# 13thISE_ver5.net
KiCad netlist of a schematic drawn in EAGLE
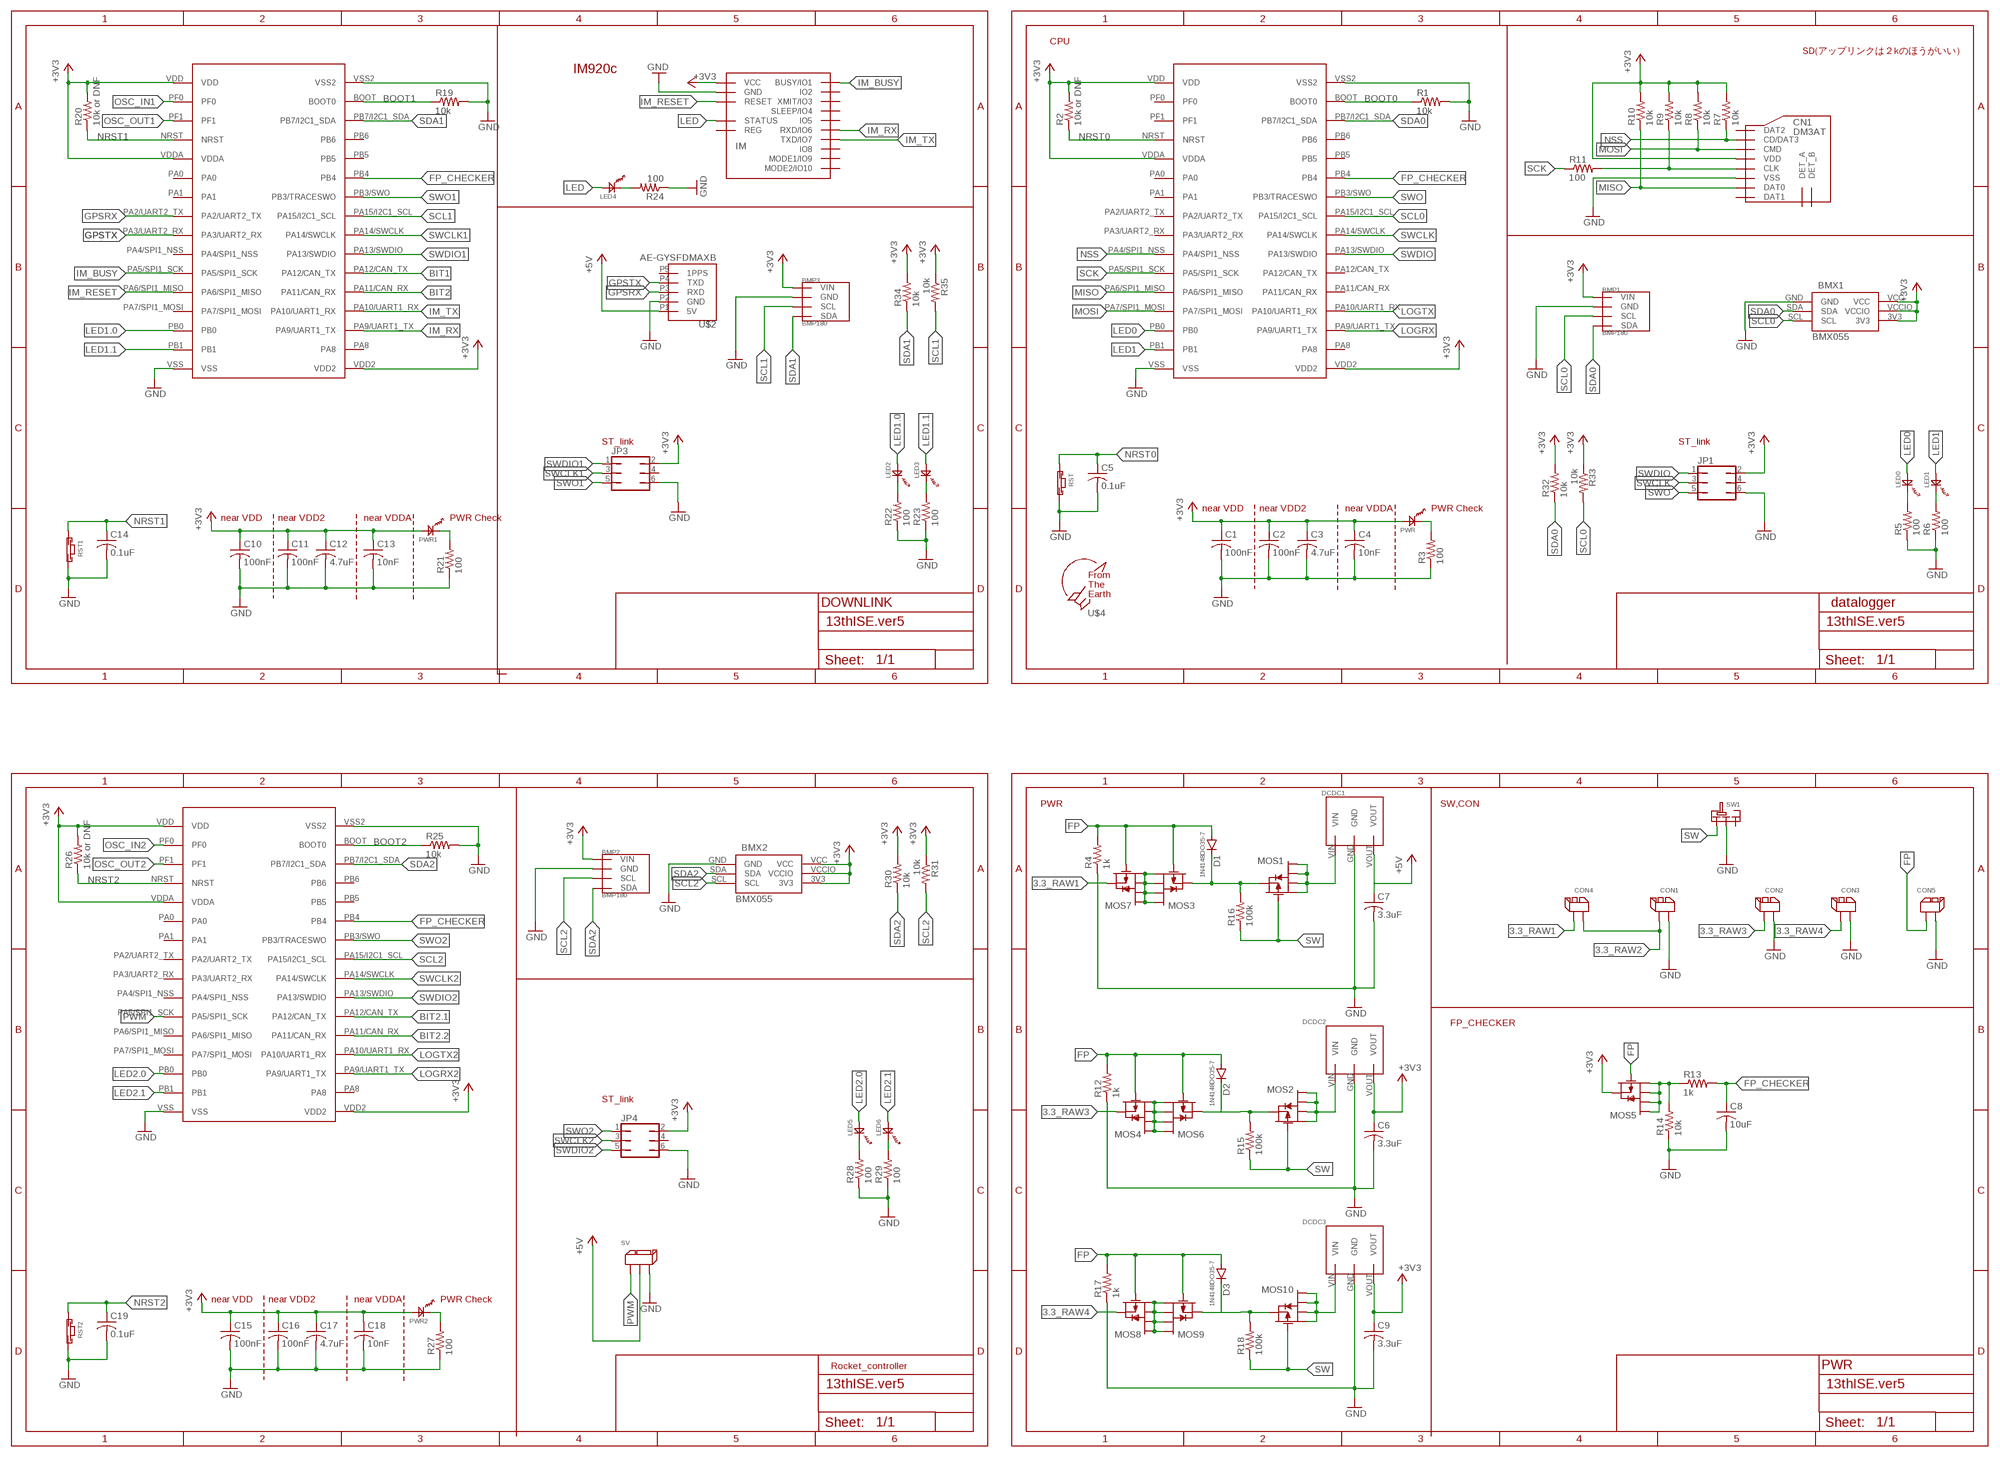
[diagram p0: schematic, sheet 1]

(export (version "E")
  (design (tool "Eeschema 10.0.6"))
  (components
    (comp (ref "BMP1")
      (value "BMP180")
      (footprint "eagle-import:GY-68")
      (libsource (lib "eagle-import") (part "BMP180"))
    )
    (comp (ref "BMP2")
      (value "BMP180")
      (footprint "eagle-import:GY-68")
      (libsource (lib "eagle-import") (part "BMP180"))
    )
    (comp (ref "BMP3")
      (value "BMP180")
      (footprint "eagle-import:GY-68")
      (libsource (lib "eagle-import") (part "BMP180"))
    )
    (comp (ref "BMX1")
      (value "BMX055")
      (footprint "eagle-import:BMX055")
      (libsource (lib "eagle-import") (part "BMX055"))
    )
    (comp (ref "BMX2")
      (value "BMX055")
      (footprint "eagle-import:BMX055")
      (libsource (lib "eagle-import") (part "BMX055"))
    )
    (comp (ref "C1")
      (value "100nF")
      (footprint "eagle-import:C1608")
      (libsource (lib "eagle-import") (part "C-USC1608"))
    )
    (comp (ref "C2")
      (value "100nF")
      (footprint "eagle-import:C1608")
      (libsource (lib "eagle-import") (part "C-USC1608"))
    )
    (comp (ref "C3")
      (value "4.7uF")
      (footprint "eagle-import:C1608")
      (libsource (lib "eagle-import") (part "C-USC1608"))
    )
    (comp (ref "C4")
      (value "10nF")
      (footprint "eagle-import:C1608")
      (libsource (lib "eagle-import") (part "C-USC1608"))
    )
    (comp (ref "C5")
      (value "0.1uF")
      (footprint "eagle-import:C1608")
      (libsource (lib "eagle-import") (part "C-USC1608"))
    )
    (comp (ref "C6")
      (value "3.3uF")
      (footprint "eagle-import:C0603")
      (libsource (lib "eagle-import") (part "C-USC0603"))
    )
    (comp (ref "C7")
      (value "3.3uF")
      (footprint "eagle-import:C0603")
      (libsource (lib "eagle-import") (part "C-USC0603"))
    )
    (comp (ref "C8")
      (value "10uF")
      (footprint "eagle-import:C0603")
      (libsource (lib "eagle-import") (part "C-USC0603"))
    )
    (comp (ref "C9")
      (value "3.3uF")
      (footprint "eagle-import:C0603")
      (libsource (lib "eagle-import") (part "C-USC0603"))
    )
    (comp (ref "C10")
      (value "100nF")
      (footprint "eagle-import:C1608")
      (libsource (lib "eagle-import") (part "C-USC1608"))
    )
    (comp (ref "C11")
      (value "100nF")
      (footprint "eagle-import:C1608")
      (libsource (lib "eagle-import") (part "C-USC1608"))
    )
    (comp (ref "C12")
      (value "4.7uF")
      (footprint "eagle-import:C1608")
      (libsource (lib "eagle-import") (part "C-USC1608"))
    )
    (comp (ref "C13")
      (value "10nF")
      (footprint "eagle-import:C1608")
      (libsource (lib "eagle-import") (part "C-USC1608"))
    )
    (comp (ref "C14")
      (value "0.1uF")
      (footprint "eagle-import:C1608")
      (libsource (lib "eagle-import") (part "C-USC1608"))
    )
    (comp (ref "C15")
      (value "100nF")
      (footprint "eagle-import:C1608")
      (libsource (lib "eagle-import") (part "C-USC1608"))
    )
    (comp (ref "C16")
      (value "100nF")
      (footprint "eagle-import:C1608")
      (libsource (lib "eagle-import") (part "C-USC1608"))
    )
    (comp (ref "C17")
      (value "4.7uF")
      (footprint "eagle-import:C1608")
      (libsource (lib "eagle-import") (part "C-USC1608"))
    )
    (comp (ref "C18")
      (value "10nF")
      (footprint "eagle-import:C1608")
      (libsource (lib "eagle-import") (part "C-USC1608"))
    )
    (comp (ref "C19")
      (value "0.1uF")
      (footprint "eagle-import:C1608")
      (libsource (lib "eagle-import") (part "C-USC1608"))
    )
    (comp (ref "CN1")
      (value "DM3AT")
      (footprint "eagle-import:DM3AT")
      (libsource (lib "eagle-import") (part "DM3AT"))
    )
    (comp (ref "CON1")
      (value "2PIN")
      (footprint "eagle-import:2PIN")
      (libsource (lib "eagle-import") (part "2PIN"))
    )
    (comp (ref "CON2")
      (value "2PIN")
      (footprint "eagle-import:2PIN")
      (libsource (lib "eagle-import") (part "2PIN"))
    )
    (comp (ref "CON3")
      (value "2PIN")
      (footprint "eagle-import:2PIN")
      (libsource (lib "eagle-import") (part "2PIN"))
    )
    (comp (ref "CON4")
      (value "2PIN")
      (footprint "eagle-import:2PIN")
      (libsource (lib "eagle-import") (part "2PIN"))
    )
    (comp (ref "CON5")
      (value "2PIN")
      (footprint "eagle-import:2PIN")
      (libsource (lib "eagle-import") (part "2PIN"))
    )
    (comp (ref "D1")
      (value "1N4148DO35-7")
      (footprint "eagle-import:DO35-7")
      (libsource (lib "eagle-import") (part "1N4148DO35-7"))
    )
    (comp (ref "D2")
      (value "1N4148DO35-7")
      (footprint "eagle-import:DO35-7")
      (libsource (lib "eagle-import") (part "1N4148DO35-7"))
    )
    (comp (ref "D3")
      (value "1N4148DO35-7")
      (footprint "eagle-import:DO35-7")
      (libsource (lib "eagle-import") (part "1N4148DO35-7"))
    )
    (comp (ref "DCDC1")
      (value "5V1A_M78AR05-1")
      (footprint "eagle-import:5V1A_M78AR05-1")
      (libsource (lib "eagle-import") (part "5V1A_M78AR05-1"))
    )
    (comp (ref "DCDC2")
      (value "3.3V1A_M78AR033-1")
      (footprint "eagle-import:3.3V1A_M78AR033-1")
      (libsource (lib "eagle-import") (part "3.3V1A_M78AR033-1"))
    )
    (comp (ref "DCDC3")
      (value "3.3V1A_M78AR033-1")
      (footprint "eagle-import:3.3V1A_M78AR033-1")
      (libsource (lib "eagle-import") (part "3.3V1A_M78AR033-1"))
    )
    (comp (ref "IM")
      (value "IM920C")
      (footprint "eagle-import:IM920C")
      (libsource (lib "eagle-import") (part "IM920C"))
    )
    (comp (ref "JP1")
      (value "JP3Q")
      (footprint "eagle-import:JP3Q")
      (libsource (lib "eagle-import") (part "JP3Q"))
    )
    (comp (ref "JP3")
      (value "JP3Q")
      (footprint "eagle-import:JP3Q")
      (libsource (lib "eagle-import") (part "JP3Q"))
    )
    (comp (ref "JP4")
      (value "JP3Q")
      (footprint "eagle-import:JP3Q")
      (libsource (lib "eagle-import") (part "JP3Q"))
    )
    (comp (ref "LED0")
      (value "OSXX1608C1A")
      (footprint "eagle-import:OSXX1608C1A")
      (libsource (lib "eagle-import") (part "OSXX1608C1A"))
    )
    (comp (ref "LED1")
      (value "OSXX1608C1A")
      (footprint "eagle-import:OSXX1608C1A")
      (libsource (lib "eagle-import") (part "OSXX1608C1A"))
    )
    (comp (ref "LED2")
      (value "OSXX1608C1A")
      (footprint "eagle-import:OSXX1608C1A")
      (libsource (lib "eagle-import") (part "OSXX1608C1A"))
    )
    (comp (ref "LED3")
      (value "OSXX1608C1A")
      (footprint "eagle-import:OSXX1608C1A")
      (libsource (lib "eagle-import") (part "OSXX1608C1A"))
    )
    (comp (ref "LED4")
      (value "OSXX1608C1A")
      (footprint "eagle-import:OSXX1608C1A")
      (libsource (lib "eagle-import") (part "OSXX1608C1A"))
    )
    (comp (ref "LED5")
      (value "OSXX1608C1A")
      (footprint "eagle-import:OSXX1608C1A")
      (libsource (lib "eagle-import") (part "OSXX1608C1A"))
    )
    (comp (ref "LED6")
      (value "OSXX1608C1A")
      (footprint "eagle-import:OSXX1608C1A")
      (libsource (lib "eagle-import") (part "OSXX1608C1A"))
    )
    (comp (ref "MOS1")
      (value "PCH_SSM6J808R")
      (footprint "eagle-import:SSM6J808R")
      (libsource (lib "eagle-import") (part "PCH_SSM6J808R"))
    )
    (comp (ref "MOS2")
      (value "PCH_SSM6J808R")
      (footprint "eagle-import:SSM6J808R")
      (libsource (lib "eagle-import") (part "PCH_SSM6J808R"))
    )
    (comp (ref "MOS3")
      (value "PCH_SSM6J808R")
      (footprint "eagle-import:SSM6J808R")
      (libsource (lib "eagle-import") (part "PCH_SSM6J808R"))
    )
    (comp (ref "MOS4")
      (value "PCH_SSM6J808R")
      (footprint "eagle-import:SSM6J808R")
      (libsource (lib "eagle-import") (part "PCH_SSM6J808R"))
    )
    (comp (ref "MOS5")
      (value "PCH_SSM6J808R")
      (footprint "eagle-import:SSM6J808R")
      (libsource (lib "eagle-import") (part "PCH_SSM6J808R"))
    )
    (comp (ref "MOS6")
      (value "PCH_SSM6J808R")
      (footprint "eagle-import:SSM6J808R")
      (libsource (lib "eagle-import") (part "PCH_SSM6J808R"))
    )
    (comp (ref "MOS7")
      (value "PCH_SSM6J808R")
      (footprint "eagle-import:SSM6J808R")
      (libsource (lib "eagle-import") (part "PCH_SSM6J808R"))
    )
    (comp (ref "MOS8")
      (value "PCH_SSM6J808R")
      (footprint "eagle-import:SSM6J808R")
      (libsource (lib "eagle-import") (part "PCH_SSM6J808R"))
    )
    (comp (ref "MOS9")
      (value "PCH_SSM6J808R")
      (footprint "eagle-import:SSM6J808R")
      (libsource (lib "eagle-import") (part "PCH_SSM6J808R"))
    )
    (comp (ref "MOS10")
      (value "PCH_SSM6J808R")
      (footprint "eagle-import:SSM6J808R")
      (libsource (lib "eagle-import") (part "PCH_SSM6J808R"))
    )
    (comp (ref "PWR")
      (value "OSXX1608C1A")
      (footprint "eagle-import:OSXX1608C1A")
      (libsource (lib "eagle-import") (part "OSXX1608C1A"))
    )
    (comp (ref "PWR1")
      (value "OSXX1608C1A")
      (footprint "eagle-import:OSXX1608C1A")
      (libsource (lib "eagle-import") (part "OSXX1608C1A"))
    )
    (comp (ref "PWR2")
      (value "OSXX1608C1A")
      (footprint "eagle-import:OSXX1608C1A")
      (libsource (lib "eagle-import") (part "OSXX1608C1A"))
    )
    (comp (ref "R1")
      (value "10k")
      (footprint "eagle-import:R0603")
      (libsource (lib "eagle-import") (part "R-US_R0603"))
    )
    (comp (ref "R2")
      (value "10k or DNF")
      (footprint "eagle-import:R0603")
      (libsource (lib "eagle-import") (part "R-US_R0603"))
    )
    (comp (ref "R3")
      (value "100")
      (footprint "eagle-import:R0603")
      (libsource (lib "eagle-import") (part "R-US_R0603"))
    )
    (comp (ref "R4")
      (value "1k")
      (footprint "eagle-import:R0603")
      (libsource (lib "eagle-import") (part "R-US_R0603"))
    )
    (comp (ref "R5")
      (value "100")
      (footprint "eagle-import:R0603")
      (libsource (lib "eagle-import") (part "R-US_R0603"))
    )
    (comp (ref "R6")
      (value "100")
      (footprint "eagle-import:R0603")
      (libsource (lib "eagle-import") (part "R-US_R0603"))
    )
    (comp (ref "R7")
      (value "10k")
      (footprint "eagle-import:R0603")
      (libsource (lib "eagle-import") (part "R-US_R0603"))
    )
    (comp (ref "R8")
      (value "10k")
      (footprint "eagle-import:R0603")
      (libsource (lib "eagle-import") (part "R-US_R0603"))
    )
    (comp (ref "R9")
      (value "10k")
      (footprint "eagle-import:R0603")
      (libsource (lib "eagle-import") (part "R-US_R0603"))
    )
    (comp (ref "R10")
      (value "10k")
      (footprint "eagle-import:R0603")
      (libsource (lib "eagle-import") (part "R-US_R0603"))
    )
    (comp (ref "R11")
      (value "100")
      (footprint "eagle-import:R0603")
      (libsource (lib "eagle-import") (part "R-US_R0603"))
    )
    (comp (ref "R12")
      (value "1k")
      (footprint "eagle-import:R0603")
      (libsource (lib "eagle-import") (part "R-US_R0603"))
    )
    (comp (ref "R13")
      (value "1k")
      (footprint "eagle-import:R0603")
      (libsource (lib "eagle-import") (part "R-US_R0603"))
    )
    (comp (ref "R14")
      (value "10k")
      (footprint "eagle-import:R0603")
      (libsource (lib "eagle-import") (part "R-US_R0603"))
    )
    (comp (ref "R15")
      (value "100k")
      (footprint "eagle-import:R0603")
      (libsource (lib "eagle-import") (part "R-US_R0603"))
    )
    (comp (ref "R16")
      (value "100k")
      (footprint "eagle-import:R0603")
      (libsource (lib "eagle-import") (part "R-US_R0603"))
    )
    (comp (ref "R17")
      (value "1k")
      (footprint "eagle-import:R0603")
      (libsource (lib "eagle-import") (part "R-US_R0603"))
    )
    (comp (ref "R18")
      (value "100k")
      (footprint "eagle-import:R0603")
      (libsource (lib "eagle-import") (part "R-US_R0603"))
    )
    (comp (ref "R19")
      (value "10k")
      (footprint "eagle-import:R0603")
      (libsource (lib "eagle-import") (part "R-US_R0603"))
    )
    (comp (ref "R20")
      (value "10k or DNF")
      (footprint "eagle-import:R0603")
      (libsource (lib "eagle-import") (part "R-US_R0603"))
    )
    (comp (ref "R21")
      (value "100")
      (footprint "eagle-import:R0603")
      (libsource (lib "eagle-import") (part "R-US_R0603"))
    )
    (comp (ref "R22")
      (value "100")
      (footprint "eagle-import:R0603")
      (libsource (lib "eagle-import") (part "R-US_R0603"))
    )
    (comp (ref "R23")
      (value "100")
      (footprint "eagle-import:R0603")
      (libsource (lib "eagle-import") (part "R-US_R0603"))
    )
    (comp (ref "R24")
      (value "100")
      (footprint "eagle-import:R0603")
      (libsource (lib "eagle-import") (part "R-US_R0603"))
    )
    (comp (ref "R25")
      (value "10k")
      (footprint "eagle-import:R0603")
      (libsource (lib "eagle-import") (part "R-US_R0603"))
    )
    (comp (ref "R26")
      (value "10k or DNF")
      (footprint "eagle-import:R0603")
      (libsource (lib "eagle-import") (part "R-US_R0603"))
    )
    (comp (ref "R27")
      (value "100")
      (footprint "eagle-import:R0603")
      (libsource (lib "eagle-import") (part "R-US_R0603"))
    )
    (comp (ref "R28")
      (value "100")
      (footprint "eagle-import:R0603")
      (libsource (lib "eagle-import") (part "R-US_R0603"))
    )
    (comp (ref "R29")
      (value "100")
      (footprint "eagle-import:R0603")
      (libsource (lib "eagle-import") (part "R-US_R0603"))
    )
    (comp (ref "R30")
      (value "10k")
      (footprint "eagle-import:R0603")
      (libsource (lib "eagle-import") (part "R-US_R0603"))
    )
    (comp (ref "R31")
      (value "10k")
      (footprint "eagle-import:R0603")
      (libsource (lib "eagle-import") (part "R-US_R0603"))
    )
    (comp (ref "R32")
      (value "10k")
      (footprint "eagle-import:R0603")
      (libsource (lib "eagle-import") (part "R-US_R0603"))
    )
    (comp (ref "R33")
      (value "10k")
      (footprint "eagle-import:R0603")
      (libsource (lib "eagle-import") (part "R-US_R0603"))
    )
    (comp (ref "R34")
      (value "10k")
      (footprint "eagle-import:R0603")
      (libsource (lib "eagle-import") (part "R-US_R0603"))
    )
    (comp (ref "R35")
      (value "10k")
      (footprint "eagle-import:R0603")
      (libsource (lib "eagle-import") (part "R-US_R0603"))
    )
    (comp (ref "RST")
      (value "TVAF06-A020B-R")
      (footprint "eagle-import:TVAF06-A020B-R")
      (libsource (lib "eagle-import") (part "TVAF06-A020B-R"))
    )
    (comp (ref "RST1")
      (value "TVAF06-A020B-R")
      (footprint "eagle-import:TVAF06-A020B-R")
      (libsource (lib "eagle-import") (part "TVAF06-A020B-R"))
    )
    (comp (ref "RST2")
      (value "TVAF06-A020B-R")
      (footprint "eagle-import:TVAF06-A020B-R")
      (libsource (lib "eagle-import") (part "TVAF06-A020B-R"))
    )
    (comp (ref "STM0")
      (value "STM32F303K8")
      (footprint "eagle-import:STM32F303K8")
      (libsource (lib "eagle-import") (part "STM32F303K8"))
    )
    (comp (ref "STM1")
      (value "STM32F303K8")
      (footprint "eagle-import:STM32F303K8")
      (libsource (lib "eagle-import") (part "STM32F303K8"))
    )
    (comp (ref "SV")
      (value "3PIN")
      (footprint "eagle-import:3PIN")
      (libsource (lib "eagle-import") (part "3PIN"))
    )
    (comp (ref "SW1")
      (value "SRIDE_SWITCH")
      (footprint "eagle-import:SRIDE_SWITCH")
      (libsource (lib "eagle-import") (part "SRIDE_SWITCH"))
    )
    (comp (ref "U$1")
      (value "STM32F303K8")
      (footprint "eagle-import:STM32F303K8")
      (libsource (lib "eagle-import") (part "STM32F303K8"))
    )
    (comp (ref "U$2")
      (value "AE-GYSFDMAXB")
      (footprint "eagle-import:AE-GYSFDMAXB")
      (libsource (lib "eagle-import") (part "AE-GYSFDMAXB"))
    )
    (comp (ref "U$4")
      (value "F.T.E.LOGO")
      (footprint "eagle-import:LOGO")
      (libsource (lib "eagle-import") (part "F.T.E.LOGO"))
    )
  )
  (nets
    (net (code "1") (name "+3V3") (class "Default")
      (node (ref "BMP1") (pin "P1") (pinfunction "VIN_P1") (pintype "bidirectional"))
      (node (ref "BMP2") (pin "P1") (pinfunction "VIN_P1") (pintype "bidirectional"))
      (node (ref "BMP3") (pin "P1") (pinfunction "VIN_P1") (pintype "bidirectional"))
      (node (ref "BMX1") (pin "3V3") (pinfunction "3V3_3V3") (pintype "power_in"))
      (node (ref "BMX1") (pin "VCC") (pinfunction "VCC_VCC") (pintype "power_in"))
      (node (ref "BMX1") (pin "VCCIO") (pinfunction "VCCIO_VCCIO") (pintype "power_in"))
      (node (ref "BMX2") (pin "3V3") (pinfunction "3V3_3V3") (pintype "power_in"))
      (node (ref "BMX2") (pin "VCC") (pinfunction "VCC_VCC") (pintype "power_in"))
      (node (ref "BMX2") (pin "VCCIO") (pinfunction "VCCIO_VCCIO") (pintype "power_in"))
      (node (ref "C1") (pin "1") (pinfunction "1_1") (pintype "passive"))
      (node (ref "C10") (pin "1") (pinfunction "1_1") (pintype "passive"))
      (node (ref "C11") (pin "1") (pinfunction "1_1") (pintype "passive"))
      (node (ref "C12") (pin "1") (pinfunction "1_1") (pintype "passive"))
      (node (ref "C13") (pin "1") (pinfunction "1_1") (pintype "passive"))
      (node (ref "C15") (pin "1") (pinfunction "1_1") (pintype "passive"))
      (node (ref "C16") (pin "1") (pinfunction "1_1") (pintype "passive"))
      (node (ref "C17") (pin "1") (pinfunction "1_1") (pintype "passive"))
      (node (ref "C18") (pin "1") (pinfunction "1_1") (pintype "passive"))
      (node (ref "C2") (pin "1") (pinfunction "1_1") (pintype "passive"))
      (node (ref "C3") (pin "1") (pinfunction "1_1") (pintype "passive"))
      (node (ref "C4") (pin "1") (pinfunction "1_1") (pintype "passive"))
      (node (ref "C6") (pin "1") (pinfunction "1_1") (pintype "passive"))
      (node (ref "C9") (pin "1") (pinfunction "1_1") (pintype "passive"))
      (node (ref "CN1") (pin "VDD") (pinfunction "VDD_VDD") (pintype "bidirectional"))
      (node (ref "DCDC2") (pin "VOUT") (pinfunction "VOUT_VOUT") (pintype "bidirectional"))
      (node (ref "DCDC3") (pin "VOUT") (pinfunction "VOUT_VOUT") (pintype "bidirectional"))
      (node (ref "IM") (pin "$P17") (pinfunction "VCC_$P17") (pintype "bidirectional"))
      (node (ref "JP1") (pin "2") (pinfunction "2_2") (pintype "passive"))
      (node (ref "JP3") (pin "2") (pinfunction "2_2") (pintype "passive"))
      (node (ref "JP4") (pin "2") (pinfunction "2_2") (pintype "passive"))
      (node (ref "MOS5") (pin "4") (pinfunction "4_4") (pintype "bidirectional"))
      (node (ref "PWR") (pin "AN") (pinfunction "AN_AN") (pintype "bidirectional"))
      (node (ref "PWR1") (pin "AN") (pinfunction "AN_AN") (pintype "bidirectional"))
      (node (ref "PWR2") (pin "AN") (pinfunction "AN_AN") (pintype "bidirectional"))
      (node (ref "R10") (pin "2") (pinfunction "2_2") (pintype "passive"))
      (node (ref "R2") (pin "2") (pinfunction "2_2") (pintype "passive"))
      (node (ref "R20") (pin "2") (pinfunction "2_2") (pintype "passive"))
      (node (ref "R26") (pin "2") (pinfunction "2_2") (pintype "passive"))
      (node (ref "R30") (pin "2") (pinfunction "2_2") (pintype "passive"))
      (node (ref "R31") (pin "1") (pinfunction "1_1") (pintype "passive"))
      (node (ref "R32") (pin "2") (pinfunction "2_2") (pintype "passive"))
      (node (ref "R33") (pin "1") (pinfunction "1_1") (pintype "passive"))
      (node (ref "R34") (pin "2") (pinfunction "2_2") (pintype "passive"))
      (node (ref "R35") (pin "1") (pinfunction "1_1") (pintype "passive"))
      (node (ref "R7") (pin "2") (pinfunction "2_2") (pintype "passive"))
      (node (ref "R8") (pin "2") (pinfunction "2_2") (pintype "passive"))
      (node (ref "R9") (pin "2") (pinfunction "2_2") (pintype "passive"))
      (node (ref "STM0") (pin "VDD") (pinfunction "VDD_VDD") (pintype "power_in"))
      (node (ref "STM0") (pin "VDD2") (pinfunction "VDD2_VDD2") (pintype "power_in"))
      (node (ref "STM0") (pin "VDDA") (pinfunction "VDDA_VDDA") (pintype "power_in"))
      (node (ref "STM1") (pin "VDD") (pinfunction "VDD_VDD") (pintype "power_in"))
      (node (ref "STM1") (pin "VDD2") (pinfunction "VDD2_VDD2") (pintype "power_in"))
      (node (ref "STM1") (pin "VDDA") (pinfunction "VDDA_VDDA") (pintype "power_in"))
      (node (ref "U$1") (pin "VDD") (pinfunction "VDD_VDD") (pintype "power_in"))
      (node (ref "U$1") (pin "VDD2") (pinfunction "VDD2_VDD2") (pintype "power_in"))
      (node (ref "U$1") (pin "VDDA") (pinfunction "VDDA_VDDA") (pintype "power_in"))
    )
    (net (code "2") (name "+5V") (class "Default")
      (node (ref "C7") (pin "1") (pinfunction "1_1") (pintype "passive"))
      (node (ref "DCDC1") (pin "VOUT") (pinfunction "VOUT_VOUT") (pintype "bidirectional"))
      (node (ref "SV") (pin "P$2") (pinfunction "P$2_P$2") (pintype "bidirectional"))
      (node (ref "U$2") (pin "P1") (pinfunction "5V_P1") (pintype "bidirectional"))
    )
    (net (code "3") (name "/BOOT0") (class "Default")
      (node (ref "R1") (pin "1") (pinfunction "1_1") (pintype "passive"))
      (node (ref "STM0") (pin "BOOT") (pinfunction "BOOT0_BOOT") (pintype "bidirectional"))
    )
    (net (code "4") (name "/BOOT1") (class "Default")
      (node (ref "R19") (pin "1") (pinfunction "1_1") (pintype "passive"))
      (node (ref "STM1") (pin "BOOT") (pinfunction "BOOT0_BOOT") (pintype "bidirectional"))
    )
    (net (code "5") (name "/BOOT2") (class "Default")
      (node (ref "R25") (pin "1") (pinfunction "1_1") (pintype "passive"))
      (node (ref "U$1") (pin "BOOT") (pinfunction "BOOT0_BOOT") (pintype "bidirectional"))
    )
    (net (code "6") (name "3.3_RAW1") (class "Default")
      (node (ref "CON4") (pin "P$2") (pinfunction "P$2_P$2") (pintype "bidirectional"))
      (node (ref "MOS7") (pin "4") (pinfunction "4_4") (pintype "bidirectional"))
    )
    (net (code "7") (name "3.3_RAW2") (class "Default")
      (node (ref "CON1") (pin "P$2") (pinfunction "P$2_P$2") (pintype "bidirectional"))
      (node (ref "CON4") (pin "P$1") (pinfunction "P$1_P$1") (pintype "bidirectional"))
    )
    (net (code "8") (name "3.3_RAW3") (class "Default")
      (node (ref "CON2") (pin "P$2") (pinfunction "P$2_P$2") (pintype "bidirectional"))
      (node (ref "MOS4") (pin "4") (pinfunction "4_4") (pintype "bidirectional"))
    )
    (net (code "9") (name "3.3_RAW4") (class "Default")
      (node (ref "CON3") (pin "P$2") (pinfunction "P$2_P$2") (pintype "bidirectional"))
      (node (ref "MOS8") (pin "4") (pinfunction "4_4") (pintype "bidirectional"))
    )
    (net (code "10") (name "BIT1") (class "Default")
      (node (ref "STM1") (pin "PA12/CAN_TX") (pinfunction "PA12/CAN_TX_PA12/CAN_TX") (pintype "bidirectional"))
    )
    (net (code "11") (name "BIT2") (class "Default")
      (node (ref "STM1") (pin "PA11/CAN_RX") (pinfunction "PA11/CAN_RX_PA11/CAN_RX") (pintype "bidirectional"))
    )
    (net (code "12") (name "BIT2.1") (class "Default")
      (node (ref "U$1") (pin "PA12/CAN_TX") (pinfunction "PA12/CAN_TX_PA12/CAN_TX") (pintype "bidirectional"))
    )
    (net (code "13") (name "BIT2.2") (class "Default")
      (node (ref "U$1") (pin "PA11/CAN_RX") (pinfunction "PA11/CAN_RX_PA11/CAN_RX") (pintype "bidirectional"))
    )
    (net (code "14") (name "FP") (class "Default")
      (node (ref "CON5") (pin "P$1") (pinfunction "P$1_P$1") (pintype "bidirectional"))
      (node (ref "D1") (pin "A") (pinfunction "A_A") (pintype "passive"))
      (node (ref "D2") (pin "A") (pinfunction "A_A") (pintype "passive"))
      (node (ref "D3") (pin "A") (pinfunction "A_A") (pintype "passive"))
      (node (ref "MOS3") (pin "3") (pinfunction "3_3") (pintype "bidirectional"))
      (node (ref "MOS4") (pin "3") (pinfunction "3_3") (pintype "bidirectional"))
      (node (ref "MOS5") (pin "3") (pinfunction "3_3") (pintype "bidirectional"))
      (node (ref "MOS6") (pin "3") (pinfunction "3_3") (pintype "bidirectional"))
      (node (ref "MOS7") (pin "3") (pinfunction "3_3") (pintype "bidirectional"))
      (node (ref "MOS8") (pin "3") (pinfunction "3_3") (pintype "bidirectional"))
      (node (ref "MOS9") (pin "3") (pinfunction "3_3") (pintype "bidirectional"))
      (node (ref "R12") (pin "2") (pinfunction "2_2") (pintype "passive"))
      (node (ref "R17") (pin "2") (pinfunction "2_2") (pintype "passive"))
      (node (ref "R4") (pin "2") (pinfunction "2_2") (pintype "passive"))
    )
    (net (code "15") (name "FP_CHECKER") (class "Default")
      (node (ref "C8") (pin "1") (pinfunction "1_1") (pintype "passive"))
      (node (ref "R13") (pin "2") (pinfunction "2_2") (pintype "passive"))
      (node (ref "STM0") (pin "PB4") (pinfunction "PB4_PB4") (pintype "bidirectional"))
      (node (ref "STM1") (pin "PB4") (pinfunction "PB4_PB4") (pintype "bidirectional"))
      (node (ref "U$1") (pin "PB4") (pinfunction "PB4_PB4") (pintype "bidirectional"))
    )
    (net (code "16") (name "GND") (class "Default")
      (node (ref "BMP1") (pin "P2") (pinfunction "GND_P2") (pintype "bidirectional"))
      (node (ref "BMP2") (pin "P2") (pinfunction "GND_P2") (pintype "bidirectional"))
      (node (ref "BMP3") (pin "P2") (pinfunction "GND_P2") (pintype "bidirectional"))
      (node (ref "BMX1") (pin "GND") (pinfunction "GND_GND") (pintype "power_in"))
      (node (ref "BMX2") (pin "GND") (pinfunction "GND_GND") (pintype "power_in"))
      (node (ref "C1") (pin "2") (pinfunction "2_2") (pintype "passive"))
      (node (ref "C10") (pin "2") (pinfunction "2_2") (pintype "passive"))
      (node (ref "C11") (pin "2") (pinfunction "2_2") (pintype "passive"))
      (node (ref "C12") (pin "2") (pinfunction "2_2") (pintype "passive"))
      (node (ref "C13") (pin "2") (pinfunction "2_2") (pintype "passive"))
      (node (ref "C14") (pin "2") (pinfunction "2_2") (pintype "passive"))
      (node (ref "C15") (pin "2") (pinfunction "2_2") (pintype "passive"))
      (node (ref "C16") (pin "2") (pinfunction "2_2") (pintype "passive"))
      (node (ref "C17") (pin "2") (pinfunction "2_2") (pintype "passive"))
      (node (ref "C18") (pin "2") (pinfunction "2_2") (pintype "passive"))
      (node (ref "C19") (pin "2") (pinfunction "2_2") (pintype "passive"))
      (node (ref "C2") (pin "2") (pinfunction "2_2") (pintype "passive"))
      (node (ref "C3") (pin "2") (pinfunction "2_2") (pintype "passive"))
      (node (ref "C4") (pin "2") (pinfunction "2_2") (pintype "passive"))
      (node (ref "C5") (pin "2") (pinfunction "2_2") (pintype "passive"))
      (node (ref "C6") (pin "2") (pinfunction "2_2") (pintype "passive"))
      (node (ref "C7") (pin "2") (pinfunction "2_2") (pintype "passive"))
      (node (ref "C8") (pin "2") (pinfunction "2_2") (pintype "passive"))
      (node (ref "C9") (pin "2") (pinfunction "2_2") (pintype "passive"))
      (node (ref "CN1") (pin "VSS") (pinfunction "VSS_VSS") (pintype "bidirectional"))
      (node (ref "CON1") (pin "P$1") (pinfunction "P$1_P$1") (pintype "bidirectional"))
      (node (ref "CON2") (pin "P$1") (pinfunction "P$1_P$1") (pintype "bidirectional"))
      (node (ref "CON3") (pin "P$1") (pinfunction "P$1_P$1") (pintype "bidirectional"))
      (node (ref "CON5") (pin "P$2") (pinfunction "P$2_P$2") (pintype "bidirectional"))
      (node (ref "DCDC1") (pin "GND") (pinfunction "GND_GND") (pintype "bidirectional"))
      (node (ref "DCDC2") (pin "GND") (pinfunction "GND_GND") (pintype "bidirectional"))
      (node (ref "DCDC3") (pin "GND") (pinfunction "GND_GND") (pintype "bidirectional"))
      (node (ref "IM") (pin "$P18") (pinfunction "GND_$P18") (pintype "bidirectional"))
      (node (ref "JP1") (pin "6") (pinfunction "6_6") (pintype "passive"))
      (node (ref "JP3") (pin "6") (pinfunction "6_6") (pintype "passive"))
      (node (ref "JP4") (pin "6") (pinfunction "6_6") (pintype "passive"))
      (node (ref "R1") (pin "2") (pinfunction "2_2") (pintype "passive"))
      (node (ref "R12") (pin "1") (pinfunction "1_1") (pintype "passive"))
      (node (ref "R14") (pin "1") (pinfunction "1_1") (pintype "passive"))
      (node (ref "R17") (pin "1") (pinfunction "1_1") (pintype "passive"))
      (node (ref "R19") (pin "2") (pinfunction "2_2") (pintype "passive"))
      (node (ref "R21") (pin "1") (pinfunction "1_1") (pintype "passive"))
      (node (ref "R22") (pin "1") (pinfunction "1_1") (pintype "passive"))
      (node (ref "R23") (pin "1") (pinfunction "1_1") (pintype "passive"))
      (node (ref "R24") (pin "1") (pinfunction "1_1") (pintype "passive"))
      (node (ref "R25") (pin "2") (pinfunction "2_2") (pintype "passive"))
      (node (ref "R27") (pin "1") (pinfunction "1_1") (pintype "passive"))
      (node (ref "R28") (pin "1") (pinfunction "1_1") (pintype "passive"))
      (node (ref "R29") (pin "1") (pinfunction "1_1") (pintype "passive"))
      (node (ref "R3") (pin "1") (pinfunction "1_1") (pintype "passive"))
      (node (ref "R4") (pin "1") (pinfunction "1_1") (pintype "passive"))
      (node (ref "R5") (pin "1") (pinfunction "1_1") (pintype "passive"))
      (node (ref "R6") (pin "1") (pinfunction "1_1") (pintype "passive"))
      (node (ref "RST") (pin "P$2") (pinfunction "P$2_P$2") (pintype "bidirectional"))
      (node (ref "RST1") (pin "P$2") (pinfunction "P$2_P$2") (pintype "bidirectional"))
      (node (ref "RST2") (pin "P$2") (pinfunction "P$2_P$2") (pintype "bidirectional"))
      (node (ref "STM0") (pin "VSS") (pinfunction "VSS_VSS") (pintype "power_in"))
      (node (ref "STM0") (pin "VSS2") (pinfunction "VSS2_VSS2") (pintype "power_in"))
      (node (ref "STM1") (pin "VSS") (pinfunction "VSS_VSS") (pintype "power_in"))
      (node (ref "STM1") (pin "VSS2") (pinfunction "VSS2_VSS2") (pintype "power_in"))
      (node (ref "SV") (pin "P$3") (pinfunction "P$3_P$3") (pintype "bidirectional"))
      (node (ref "SW1") (pin "LR") (pinfunction "LR_LR") (pintype "bidirectional"))
      (node (ref "U$1") (pin "VSS") (pinfunction "VSS_VSS") (pintype "power_in"))
      (node (ref "U$1") (pin "VSS2") (pinfunction "VSS2_VSS2") (pintype "power_in"))
      (node (ref "U$2") (pin "P2") (pinfunction "GND_P2") (pintype "bidirectional"))
    )
    (net (code "17") (name "GPSRX") (class "Default")
      (node (ref "STM1") (pin "PA2/UART2_TX") (pinfunction "PA2/UART2_TX_PA2/UART2_TX") (pintype "bidirectional"))
      (node (ref "U$2") (pin "P3") (pinfunction "RXD_P3") (pintype "bidirectional"))
    )
    (net (code "18") (name "GPSTX") (class "Default")
      (node (ref "STM1") (pin "PA3/UART2_RX") (pinfunction "PA3/UART2_RX_PA3/UART2_RX") (pintype "bidirectional"))
      (node (ref "U$2") (pin "P4") (pinfunction "TXD_P4") (pintype "bidirectional"))
    )
    (net (code "19") (name "IM_BUSY") (class "Default")
      (node (ref "IM") (pin "$P1") (pinfunction "BUSY/IO1_$P1") (pintype "bidirectional"))
      (node (ref "STM1") (pin "PA5/SPI1_SCK") (pinfunction "PA5/SPI1_SCK_PA5/SPI1_SCK") (pintype "bidirectional"))
    )
    (net (code "20") (name "IM_RESET") (class "Default")
      (node (ref "IM") (pin "$P19") (pinfunction "RESET_$P19") (pintype "bidirectional"))
      (node (ref "STM1") (pin "PA6/SPI1_MISO") (pinfunction "PA6/SPI1_MISO_PA6/SPI1_MISO") (pintype "bidirectional"))
    )
    (net (code "21") (name "IM_RX") (class "Default")
      (node (ref "IM") (pin "$P6") (pinfunction "RXD/IO6_$P6") (pintype "bidirectional"))
      (node (ref "STM1") (pin "PA9/UART1_TX") (pinfunction "PA9/UART1_TX_PA9/UART1_TX") (pintype "bidirectional"))
    )
    (net (code "22") (name "IM_TX") (class "Default")
      (node (ref "IM") (pin "$P7") (pinfunction "TXD/IO7_$P7") (pintype "bidirectional"))
      (node (ref "STM1") (pin "PA10/UART1_RX") (pinfunction "PA10/UART1_RX_PA10/UART1_RX") (pintype "bidirectional"))
    )
    (net (code "23") (name "LED") (class "Default")
      (node (ref "IM") (pin "$P15") (pinfunction "STATUS_$P15") (pintype "bidirectional"))
      (node (ref "LED4") (pin "AN") (pinfunction "AN_AN") (pintype "bidirectional"))
    )
    (net (code "24") (name "LED0") (class "Default")
      (node (ref "LED0") (pin "AN") (pinfunction "AN_AN") (pintype "bidirectional"))
      (node (ref "STM0") (pin "PB0") (pinfunction "PB0_PB0") (pintype "bidirectional"))
    )
    (net (code "25") (name "LED1") (class "Default")
      (node (ref "LED1") (pin "AN") (pinfunction "AN_AN") (pintype "bidirectional"))
      (node (ref "STM0") (pin "PB1") (pinfunction "PB1_PB1") (pintype "bidirectional"))
    )
    (net (code "26") (name "LED1.0") (class "Default")
      (node (ref "LED2") (pin "AN") (pinfunction "AN_AN") (pintype "bidirectional"))
      (node (ref "STM1") (pin "PB0") (pinfunction "PB0_PB0") (pintype "bidirectional"))
    )
    (net (code "27") (name "LED1.1") (class "Default")
      (node (ref "LED3") (pin "AN") (pinfunction "AN_AN") (pintype "bidirectional"))
      (node (ref "STM1") (pin "PB1") (pinfunction "PB1_PB1") (pintype "bidirectional"))
    )
    (net (code "28") (name "LED2.0") (class "Default")
      (node (ref "LED5") (pin "AN") (pinfunction "AN_AN") (pintype "bidirectional"))
      (node (ref "U$1") (pin "PB0") (pinfunction "PB0_PB0") (pintype "bidirectional"))
    )
    (net (code "29") (name "LED2.1") (class "Default")
      (node (ref "LED6") (pin "AN") (pinfunction "AN_AN") (pintype "bidirectional"))
      (node (ref "U$1") (pin "PB1") (pinfunction "PB1_PB1") (pintype "bidirectional"))
    )
    (net (code "30") (name "LOGRX") (class "Default")
      (node (ref "STM0") (pin "PA9/UART1_TX") (pinfunction "PA9/UART1_TX_PA9/UART1_TX") (pintype "bidirectional"))
    )
    (net (code "31") (name "LOGRX2") (class "Default")
      (node (ref "U$1") (pin "PA9/UART1_TX") (pinfunction "PA9/UART1_TX_PA9/UART1_TX") (pintype "bidirectional"))
    )
    (net (code "32") (name "LOGTX") (class "Default")
      (node (ref "STM0") (pin "PA10/UART1_RX") (pinfunction "PA10/UART1_RX_PA10/UART1_RX") (pintype "bidirectional"))
    )
    (net (code "33") (name "LOGTX2") (class "Default")
      (node (ref "U$1") (pin "PA10/UART1_RX") (pinfunction "PA10/UART1_RX_PA10/UART1_RX") (pintype "bidirectional"))
    )
    (net (code "34") (name "MISO") (class "Default")
      (node (ref "CN1") (pin "DAT0") (pinfunction "DAT0_DAT0") (pintype "bidirectional"))
      (node (ref "R10") (pin "1") (pinfunction "1_1") (pintype "passive"))
      (node (ref "STM0") (pin "PA6/SPI1_MISO") (pinfunction "PA6/SPI1_MISO_PA6/SPI1_MISO") (pintype "bidirectional"))
    )
    (net (code "35") (name "MOSI") (class "Default")
      (node (ref "CN1") (pin "CMD") (pinfunction "CMD_CMD") (pintype "bidirectional"))
      (node (ref "R8") (pin "1") (pinfunction "1_1") (pintype "passive"))
      (node (ref "STM0") (pin "PA7/SPI1_MOSI") (pinfunction "PA7/SPI1_MOSI_PA7/SPI1_MOSI") (pintype "bidirectional"))
    )
    (net (code "36") (name "NRST0") (class "Default")
      (node (ref "C5") (pin "1") (pinfunction "1_1") (pintype "passive"))
      (node (ref "R2") (pin "1") (pinfunction "1_1") (pintype "passive"))
      (node (ref "RST") (pin "P$1") (pinfunction "P$1_P$1") (pintype "bidirectional"))
      (node (ref "STM0") (pin "NRST") (pinfunction "NRST_NRST") (pintype "bidirectional"))
    )
    (net (code "37") (name "NRST1") (class "Default")
      (node (ref "C14") (pin "1") (pinfunction "1_1") (pintype "passive"))
      (node (ref "R20") (pin "1") (pinfunction "1_1") (pintype "passive"))
      (node (ref "RST1") (pin "P$1") (pinfunction "P$1_P$1") (pintype "bidirectional"))
      (node (ref "STM1") (pin "NRST") (pinfunction "NRST_NRST") (pintype "bidirectional"))
    )
    (net (code "38") (name "NRST2") (class "Default")
      (node (ref "C19") (pin "1") (pinfunction "1_1") (pintype "passive"))
      (node (ref "R26") (pin "1") (pinfunction "1_1") (pintype "passive"))
      (node (ref "RST2") (pin "P$1") (pinfunction "P$1_P$1") (pintype "bidirectional"))
      (node (ref "U$1") (pin "NRST") (pinfunction "NRST_NRST") (pintype "bidirectional"))
    )
    (net (code "39") (name "NSS") (class "Default")
      (node (ref "CN1") (pin "CD/DAT3") (pinfunction "CD/DAT3_CD/DAT3") (pintype "bidirectional"))
      (node (ref "R7") (pin "1") (pinfunction "1_1") (pintype "passive"))
      (node (ref "STM0") (pin "PA4/SPI1_NSS") (pinfunction "PA4/SPI1_NSS_PA4/SPI1_NSS") (pintype "bidirectional"))
    )
    (net (code "40") (name "Net-(CN1-PadCLK)") (class "Default")
      (node (ref "CN1") (pin "CLK") (pinfunction "CLK_CLK") (pintype "bidirectional"))
      (node (ref "R11") (pin "2") (pinfunction "2_2") (pintype "passive"))
      (node (ref "R9") (pin "1") (pinfunction "1_1") (pintype "passive"))
    )
    (net (code "41") (name "Net-(D1-PadC)") (class "Default")
      (node (ref "D1") (pin "C") (pinfunction "C_C") (pintype "passive"))
      (node (ref "MOS1") (pin "4") (pinfunction "4_4") (pintype "bidirectional"))
      (node (ref "MOS3") (pin "4") (pinfunction "4_4") (pintype "bidirectional"))
      (node (ref "R16") (pin "2") (pinfunction "2_2") (pintype "passive"))
    )
    (net (code "42") (name "Net-(D2-PadC)") (class "Default")
      (node (ref "D2") (pin "C") (pinfunction "C_C") (pintype "passive"))
      (node (ref "MOS2") (pin "4") (pinfunction "4_4") (pintype "bidirectional"))
      (node (ref "MOS6") (pin "4") (pinfunction "4_4") (pintype "bidirectional"))
      (node (ref "R15") (pin "2") (pinfunction "2_2") (pintype "passive"))
    )
    (net (code "43") (name "Net-(D3-PadC)") (class "Default")
      (node (ref "D3") (pin "C") (pinfunction "C_C") (pintype "passive"))
      (node (ref "MOS10") (pin "4") (pinfunction "4_4") (pintype "bidirectional"))
      (node (ref "MOS9") (pin "4") (pinfunction "4_4") (pintype "bidirectional"))
      (node (ref "R18") (pin "2") (pinfunction "2_2") (pintype "passive"))
    )
    (net (code "44") (name "Net-(DCDC1-PadVIN)") (class "Default")
      (node (ref "DCDC1") (pin "VIN") (pinfunction "VIN_VIN") (pintype "bidirectional"))
      (node (ref "MOS1") (pin "1") (pinfunction "1_1") (pintype "bidirectional"))
      (node (ref "MOS1") (pin "2") (pinfunction "2_2") (pintype "bidirectional"))
      (node (ref "MOS1") (pin "5") (pinfunction "5_5") (pintype "bidirectional"))
      (node (ref "MOS1") (pin "6") (pinfunction "6_6") (pintype "bidirectional"))
    )
    (net (code "45") (name "Net-(DCDC2-PadVIN)") (class "Default")
      (node (ref "DCDC2") (pin "VIN") (pinfunction "VIN_VIN") (pintype "bidirectional"))
      (node (ref "MOS2") (pin "1") (pinfunction "1_1") (pintype "bidirectional"))
      (node (ref "MOS2") (pin "2") (pinfunction "2_2") (pintype "bidirectional"))
      (node (ref "MOS2") (pin "5") (pinfunction "5_5") (pintype "bidirectional"))
      (node (ref "MOS2") (pin "6") (pinfunction "6_6") (pintype "bidirectional"))
    )
    (net (code "46") (name "Net-(DCDC3-PadVIN)") (class "Default")
      (node (ref "DCDC3") (pin "VIN") (pinfunction "VIN_VIN") (pintype "bidirectional"))
      (node (ref "MOS10") (pin "1") (pinfunction "1_1") (pintype "bidirectional"))
      (node (ref "MOS10") (pin "2") (pinfunction "2_2") (pintype "bidirectional"))
      (node (ref "MOS10") (pin "5") (pinfunction "5_5") (pintype "bidirectional"))
      (node (ref "MOS10") (pin "6") (pinfunction "6_6") (pintype "bidirectional"))
    )
    (net (code "47") (name "Net-(LED0-PadCT)") (class "Default")
      (node (ref "LED0") (pin "CT") (pinfunction "CT_CT") (pintype "bidirectional"))
      (node (ref "R5") (pin "2") (pinfunction "2_2") (pintype "passive"))
    )
    (net (code "48") (name "Net-(LED1-PadCT)") (class "Default")
      (node (ref "LED1") (pin "CT") (pinfunction "CT_CT") (pintype "bidirectional"))
      (node (ref "R6") (pin "2") (pinfunction "2_2") (pintype "passive"))
    )
    (net (code "49") (name "Net-(LED2-PadCT)") (class "Default")
      (node (ref "LED2") (pin "CT") (pinfunction "CT_CT") (pintype "bidirectional"))
      (node (ref "R22") (pin "2") (pinfunction "2_2") (pintype "passive"))
    )
    (net (code "50") (name "Net-(LED3-PadCT)") (class "Default")
      (node (ref "LED3") (pin "CT") (pinfunction "CT_CT") (pintype "bidirectional"))
      (node (ref "R23") (pin "2") (pinfunction "2_2") (pintype "passive"))
    )
    (net (code "51") (name "Net-(LED4-PadCT)") (class "Default")
      (node (ref "LED4") (pin "CT") (pinfunction "CT_CT") (pintype "bidirectional"))
      (node (ref "R24") (pin "2") (pinfunction "2_2") (pintype "passive"))
    )
    (net (code "52") (name "Net-(LED5-PadCT)") (class "Default")
      (node (ref "LED5") (pin "CT") (pinfunction "CT_CT") (pintype "bidirectional"))
      (node (ref "R28") (pin "2") (pinfunction "2_2") (pintype "passive"))
    )
    (net (code "53") (name "Net-(LED6-PadCT)") (class "Default")
      (node (ref "LED6") (pin "CT") (pinfunction "CT_CT") (pintype "bidirectional"))
      (node (ref "R29") (pin "2") (pinfunction "2_2") (pintype "passive"))
    )
    (net (code "54") (name "Net-(MOS3-Pad1)") (class "Default")
      (node (ref "MOS3") (pin "1") (pinfunction "1_1") (pintype "bidirectional"))
      (node (ref "MOS3") (pin "2") (pinfunction "2_2") (pintype "bidirectional"))
      (node (ref "MOS3") (pin "5") (pinfunction "5_5") (pintype "bidirectional"))
      (node (ref "MOS3") (pin "6") (pinfunction "6_6") (pintype "bidirectional"))
      (node (ref "MOS7") (pin "1") (pinfunction "1_1") (pintype "bidirectional"))
      (node (ref "MOS7") (pin "2") (pinfunction "2_2") (pintype "bidirectional"))
      (node (ref "MOS7") (pin "5") (pinfunction "5_5") (pintype "bidirectional"))
      (node (ref "MOS7") (pin "6") (pinfunction "6_6") (pintype "bidirectional"))
    )
    (net (code "55") (name "Net-(MOS4-Pad1)") (class "Default")
      (node (ref "MOS4") (pin "1") (pinfunction "1_1") (pintype "bidirectional"))
      (node (ref "MOS4") (pin "2") (pinfunction "2_2") (pintype "bidirectional"))
      (node (ref "MOS4") (pin "5") (pinfunction "5_5") (pintype "bidirectional"))
      (node (ref "MOS4") (pin "6") (pinfunction "6_6") (pintype "bidirectional"))
      (node (ref "MOS6") (pin "1") (pinfunction "1_1") (pintype "bidirectional"))
      (node (ref "MOS6") (pin "2") (pinfunction "2_2") (pintype "bidirectional"))
      (node (ref "MOS6") (pin "5") (pinfunction "5_5") (pintype "bidirectional"))
      (node (ref "MOS6") (pin "6") (pinfunction "6_6") (pintype "bidirectional"))
    )
    (net (code "56") (name "Net-(MOS5-Pad1)") (class "Default")
      (node (ref "MOS5") (pin "1") (pinfunction "1_1") (pintype "bidirectional"))
      (node (ref "MOS5") (pin "2") (pinfunction "2_2") (pintype "bidirectional"))
      (node (ref "MOS5") (pin "5") (pinfunction "5_5") (pintype "bidirectional"))
      (node (ref "MOS5") (pin "6") (pinfunction "6_6") (pintype "bidirectional"))
      (node (ref "R13") (pin "1") (pinfunction "1_1") (pintype "passive"))
      (node (ref "R14") (pin "2") (pinfunction "2_2") (pintype "passive"))
    )
    (net (code "57") (name "Net-(MOS8-Pad1)") (class "Default")
      (node (ref "MOS8") (pin "1") (pinfunction "1_1") (pintype "bidirectional"))
      (node (ref "MOS8") (pin "2") (pinfunction "2_2") (pintype "bidirectional"))
      (node (ref "MOS8") (pin "5") (pinfunction "5_5") (pintype "bidirectional"))
      (node (ref "MOS8") (pin "6") (pinfunction "6_6") (pintype "bidirectional"))
      (node (ref "MOS9") (pin "1") (pinfunction "1_1") (pintype "bidirectional"))
      (node (ref "MOS9") (pin "2") (pinfunction "2_2") (pintype "bidirectional"))
      (node (ref "MOS9") (pin "5") (pinfunction "5_5") (pintype "bidirectional"))
      (node (ref "MOS9") (pin "6") (pinfunction "6_6") (pintype "bidirectional"))
    )
    (net (code "58") (name "Net-(PWR-PadCT)") (class "Default")
      (node (ref "PWR") (pin "CT") (pinfunction "CT_CT") (pintype "bidirectional"))
      (node (ref "R3") (pin "2") (pinfunction "2_2") (pintype "passive"))
    )
    (net (code "59") (name "Net-(PWR1-PadCT)") (class "Default")
      (node (ref "PWR1") (pin "CT") (pinfunction "CT_CT") (pintype "bidirectional"))
      (node (ref "R21") (pin "2") (pinfunction "2_2") (pintype "passive"))
    )
    (net (code "60") (name "Net-(PWR2-PadCT)") (class "Default")
      (node (ref "PWR2") (pin "CT") (pinfunction "CT_CT") (pintype "bidirectional"))
      (node (ref "R27") (pin "2") (pinfunction "2_2") (pintype "passive"))
    )
    (net (code "61") (name "OSC_IN1") (class "Default")
      (node (ref "STM1") (pin "PF0") (pinfunction "PF0_PF0") (pintype "bidirectional"))
    )
    (net (code "62") (name "OSC_IN2") (class "Default")
      (node (ref "U$1") (pin "PF0") (pinfunction "PF0_PF0") (pintype "bidirectional"))
    )
    (net (code "63") (name "OSC_OUT1") (class "Default")
      (node (ref "STM1") (pin "PF1") (pinfunction "PF1_PF1") (pintype "bidirectional"))
    )
    (net (code "64") (name "OSC_OUT2") (class "Default")
      (node (ref "U$1") (pin "PF1") (pinfunction "PF1_PF1") (pintype "bidirectional"))
    )
    (net (code "65") (name "PWM") (class "Default")
      (node (ref "SV") (pin "P$1") (pinfunction "P$1_P$1") (pintype "bidirectional"))
      (node (ref "U$1") (pin "PA5/SPI1_SCK") (pinfunction "PA5/SPI1_SCK_PA5/SPI1_SCK") (pintype "bidirectional"))
    )
    (net (code "66") (name "SCK") (class "Default")
      (node (ref "R11") (pin "1") (pinfunction "1_1") (pintype "passive"))
      (node (ref "STM0") (pin "PA5/SPI1_SCK") (pinfunction "PA5/SPI1_SCK_PA5/SPI1_SCK") (pintype "bidirectional"))
    )
    (net (code "67") (name "SCL0") (class "Default")
      (node (ref "BMP1") (pin "P3") (pinfunction "SCL_P3") (pintype "bidirectional"))
      (node (ref "BMX1") (pin "SCL") (pinfunction "SCL_SCL") (pintype "bidirectional"))
      (node (ref "R33") (pin "2") (pinfunction "2_2") (pintype "passive"))
      (node (ref "STM0") (pin "PA15/I2C1_SCL") (pinfunction "PA15/I2C1_SCL_PA15/I2C1_SCL") (pintype "bidirectional"))
    )
    (net (code "68") (name "SCL1") (class "Default")
      (node (ref "BMP3") (pin "P3") (pinfunction "SCL_P3") (pintype "bidirectional"))
      (node (ref "R35") (pin "2") (pinfunction "2_2") (pintype "passive"))
      (node (ref "STM1") (pin "PA15/I2C1_SCL") (pinfunction "PA15/I2C1_SCL_PA15/I2C1_SCL") (pintype "bidirectional"))
    )
    (net (code "69") (name "SCL2") (class "Default")
      (node (ref "BMP2") (pin "P3") (pinfunction "SCL_P3") (pintype "bidirectional"))
      (node (ref "BMX2") (pin "SCL") (pinfunction "SCL_SCL") (pintype "bidirectional"))
      (node (ref "R31") (pin "2") (pinfunction "2_2") (pintype "passive"))
      (node (ref "U$1") (pin "PA15/I2C1_SCL") (pinfunction "PA15/I2C1_SCL_PA15/I2C1_SCL") (pintype "bidirectional"))
    )
    (net (code "70") (name "SDA0") (class "Default")
      (node (ref "BMP1") (pin "P4") (pinfunction "SDA_P4") (pintype "bidirectional"))
      (node (ref "BMX1") (pin "SDA") (pinfunction "SDA_SDA") (pintype "bidirectional"))
      (node (ref "R32") (pin "1") (pinfunction "1_1") (pintype "passive"))
      (node (ref "STM0") (pin "PB7/I2C1_SDA") (pinfunction "PB7/I2C1_SDA_PB7/I2C1_SDA") (pintype "bidirectional"))
    )
    (net (code "71") (name "SDA1") (class "Default")
      (node (ref "BMP3") (pin "P4") (pinfunction "SDA_P4") (pintype "bidirectional"))
      (node (ref "R34") (pin "1") (pinfunction "1_1") (pintype "passive"))
      (node (ref "STM1") (pin "PB7/I2C1_SDA") (pinfunction "PB7/I2C1_SDA_PB7/I2C1_SDA") (pintype "bidirectional"))
    )
    (net (code "72") (name "SDA2") (class "Default")
      (node (ref "BMP2") (pin "P4") (pinfunction "SDA_P4") (pintype "bidirectional"))
      (node (ref "BMX2") (pin "SDA") (pinfunction "SDA_SDA") (pintype "bidirectional"))
      (node (ref "R30") (pin "1") (pinfunction "1_1") (pintype "passive"))
      (node (ref "U$1") (pin "PB7/I2C1_SDA") (pinfunction "PB7/I2C1_SDA_PB7/I2C1_SDA") (pintype "bidirectional"))
    )
    (net (code "73") (name "SW") (class "Default")
      (node (ref "MOS1") (pin "3") (pinfunction "3_3") (pintype "bidirectional"))
      (node (ref "MOS10") (pin "3") (pinfunction "3_3") (pintype "bidirectional"))
      (node (ref "MOS2") (pin "3") (pinfunction "3_3") (pintype "bidirectional"))
      (node (ref "R15") (pin "1") (pinfunction "1_1") (pintype "passive"))
      (node (ref "R16") (pin "1") (pinfunction "1_1") (pintype "passive"))
      (node (ref "R18") (pin "1") (pinfunction "1_1") (pintype "passive"))
      (node (ref "SW1") (pin "L") (pinfunction "L_L") (pintype "bidirectional"))
    )
    (net (code "74") (name "SWCLK") (class "Default")
      (node (ref "JP1") (pin "3") (pinfunction "3_3") (pintype "passive"))
      (node (ref "STM0") (pin "PA14/SWCLK") (pinfunction "PA14/SWCLK_PA14/SWCLK") (pintype "bidirectional"))
    )
    (net (code "75") (name "SWCLK1") (class "Default")
      (node (ref "JP3") (pin "3") (pinfunction "3_3") (pintype "passive"))
      (node (ref "STM1") (pin "PA14/SWCLK") (pinfunction "PA14/SWCLK_PA14/SWCLK") (pintype "bidirectional"))
    )
    (net (code "76") (name "SWCLK2") (class "Default")
      (node (ref "JP4") (pin "3") (pinfunction "3_3") (pintype "passive"))
      (node (ref "U$1") (pin "PA14/SWCLK") (pinfunction "PA14/SWCLK_PA14/SWCLK") (pintype "bidirectional"))
    )
    (net (code "77") (name "SWDIO") (class "Default")
      (node (ref "JP1") (pin "1") (pinfunction "1_1") (pintype "passive"))
      (node (ref "STM0") (pin "PA13/SWDIO") (pinfunction "PA13/SWDIO_PA13/SWDIO") (pintype "bidirectional"))
    )
    (net (code "78") (name "SWDIO1") (class "Default")
      (node (ref "JP3") (pin "1") (pinfunction "1_1") (pintype "passive"))
      (node (ref "STM1") (pin "PA13/SWDIO") (pinfunction "PA13/SWDIO_PA13/SWDIO") (pintype "bidirectional"))
    )
    (net (code "79") (name "SWDIO2") (class "Default")
      (node (ref "JP4") (pin "5") (pinfunction "5_5") (pintype "passive"))
      (node (ref "U$1") (pin "PA13/SWDIO") (pinfunction "PA13/SWDIO_PA13/SWDIO") (pintype "bidirectional"))
    )
    (net (code "80") (name "SWO") (class "Default")
      (node (ref "JP1") (pin "5") (pinfunction "5_5") (pintype "passive"))
      (node (ref "STM0") (pin "PB3/SWO") (pinfunction "PB3/TRACESWO_PB3/SWO") (pintype "bidirectional"))
    )
    (net (code "81") (name "SWO1") (class "Default")
      (node (ref "JP3") (pin "5") (pinfunction "5_5") (pintype "passive"))
      (node (ref "STM1") (pin "PB3/SWO") (pinfunction "PB3/TRACESWO_PB3/SWO") (pintype "bidirectional"))
    )
    (net (code "82") (name "SWO2") (class "Default")
      (node (ref "JP4") (pin "1") (pinfunction "1_1") (pintype "passive"))
      (node (ref "U$1") (pin "PB3/SWO") (pinfunction "PB3/TRACESWO_PB3/SWO") (pintype "bidirectional"))
    )
    (net (code "83") (name "unconnected-(CN1-PadDAT1)") (class "Default")
      (node (ref "CN1") (pin "DAT1") (pinfunction "DAT1_DAT1") (pintype "bidirectional"))
    )
    (net (code "84") (name "unconnected-(CN1-PadDAT2)") (class "Default")
      (node (ref "CN1") (pin "DAT2") (pinfunction "DAT2_DAT2") (pintype "bidirectional"))
    )
    (net (code "85") (name "unconnected-(CN1-PadDET_A)") (class "Default")
      (node (ref "CN1") (pin "DET_A") (pinfunction "DET_A_DET_A") (pintype "bidirectional"))
    )
    (net (code "86") (name "unconnected-(CN1-PadDET_B)") (class "Default")
      (node (ref "CN1") (pin "DET_B") (pinfunction "DET_B_DET_B") (pintype "bidirectional"))
    )
    (net (code "87") (name "unconnected-(IM-IO2-Pad$P2)") (class "Default")
      (node (ref "IM") (pin "$P2") (pinfunction "IO2_$P2") (pintype "bidirectional"))
    )
    (net (code "88") (name "unconnected-(IM-IO5-Pad$P5)") (class "Default")
      (node (ref "IM") (pin "$P5") (pinfunction "IO5_$P5") (pintype "bidirectional"))
    )
    (net (code "89") (name "unconnected-(IM-IO8-Pad$P8)") (class "Default")
      (node (ref "IM") (pin "$P8") (pinfunction "IO8_$P8") (pintype "bidirectional"))
    )
    (net (code "90") (name "unconnected-(IM-MODE1{slash}IO9-Pad$P9)") (class "Default")
      (node (ref "IM") (pin "$P9") (pinfunction "MODE1/IO9_$P9") (pintype "bidirectional"))
    )
    (net (code "91") (name "unconnected-(IM-MODE2{slash}IO10-Pad$P10)") (class "Default")
      (node (ref "IM") (pin "$P10") (pinfunction "MODE2/IO10_$P10") (pintype "bidirectional"))
    )
    (net (code "92") (name "unconnected-(IM-REG-Pad$P16)") (class "Default")
      (node (ref "IM") (pin "$P16") (pinfunction "REG_$P16") (pintype "bidirectional"))
    )
    (net (code "93") (name "unconnected-(IM-SLEEP{slash}IO4-Pad$P4)") (class "Default")
      (node (ref "IM") (pin "$P4") (pinfunction "SLEEP/IO4_$P4") (pintype "bidirectional"))
    )
    (net (code "94") (name "unconnected-(IM-XMIT{slash}IO3-Pad$P3)") (class "Default")
      (node (ref "IM") (pin "$P3") (pinfunction "XMIT/IO3_$P3") (pintype "bidirectional"))
    )
    (net (code "95") (name "unconnected-(JP1-Pad4)") (class "Default")
      (node (ref "JP1") (pin "4") (pinfunction "4_4") (pintype "passive"))
    )
    (net (code "96") (name "unconnected-(JP3-Pad4)") (class "Default")
      (node (ref "JP3") (pin "4") (pinfunction "4_4") (pintype "passive"))
    )
    (net (code "97") (name "unconnected-(JP4-Pad4)") (class "Default")
      (node (ref "JP4") (pin "4") (pinfunction "4_4") (pintype "passive"))
    )
    (net (code "98") (name "unconnected-(STM0-PadPA0)") (class "Default")
      (node (ref "STM0") (pin "PA0") (pinfunction "PA0_PA0") (pintype "bidirectional"))
    )
    (net (code "99") (name "unconnected-(STM0-PadPA1)") (class "Default")
      (node (ref "STM0") (pin "PA1") (pinfunction "PA1_PA1") (pintype "bidirectional"))
    )
    (net (code "100") (name "unconnected-(STM0-PadPA2{slash}UART2_TX)") (class "Default")
      (node (ref "STM0") (pin "PA2/UART2_TX") (pinfunction "PA2/UART2_TX_PA2/UART2_TX") (pintype "bidirectional"))
    )
    (net (code "101") (name "unconnected-(STM0-PadPA3{slash}UART2_RX)") (class "Default")
      (node (ref "STM0") (pin "PA3/UART2_RX") (pinfunction "PA3/UART2_RX_PA3/UART2_RX") (pintype "bidirectional"))
    )
    (net (code "102") (name "unconnected-(STM0-PadPA8)") (class "Default")
      (node (ref "STM0") (pin "PA8") (pinfunction "PA8_PA8") (pintype "bidirectional"))
    )
    (net (code "103") (name "unconnected-(STM0-PadPA11{slash}CAN_RX)") (class "Default")
      (node (ref "STM0") (pin "PA11/CAN_RX") (pinfunction "PA11/CAN_RX_PA11/CAN_RX") (pintype "bidirectional"))
    )
    (net (code "104") (name "unconnected-(STM0-PadPA12{slash}CAN_TX)") (class "Default")
      (node (ref "STM0") (pin "PA12/CAN_TX") (pinfunction "PA12/CAN_TX_PA12/CAN_TX") (pintype "bidirectional"))
    )
    (net (code "105") (name "unconnected-(STM0-PadPB5)") (class "Default")
      (node (ref "STM0") (pin "PB5") (pinfunction "PB5_PB5") (pintype "bidirectional"))
    )
    (net (code "106") (name "unconnected-(STM0-PadPB6)") (class "Default")
      (node (ref "STM0") (pin "PB6") (pinfunction "PB6_PB6") (pintype "bidirectional"))
    )
    (net (code "107") (name "unconnected-(STM0-PadPF0)") (class "Default")
      (node (ref "STM0") (pin "PF0") (pinfunction "PF0_PF0") (pintype "bidirectional"))
    )
    (net (code "108") (name "unconnected-(STM0-PadPF1)") (class "Default")
      (node (ref "STM0") (pin "PF1") (pinfunction "PF1_PF1") (pintype "bidirectional"))
    )
    (net (code "109") (name "unconnected-(STM1-PadPA0)") (class "Default")
      (node (ref "STM1") (pin "PA0") (pinfunction "PA0_PA0") (pintype "bidirectional"))
    )
    (net (code "110") (name "unconnected-(STM1-PadPA1)") (class "Default")
      (node (ref "STM1") (pin "PA1") (pinfunction "PA1_PA1") (pintype "bidirectional"))
    )
    (net (code "111") (name "unconnected-(STM1-PadPA4{slash}SPI1_NSS)") (class "Default")
      (node (ref "STM1") (pin "PA4/SPI1_NSS") (pinfunction "PA4/SPI1_NSS_PA4/SPI1_NSS") (pintype "bidirectional"))
    )
    (net (code "112") (name "unconnected-(STM1-PadPA7{slash}SPI1_MOSI)") (class "Default")
      (node (ref "STM1") (pin "PA7/SPI1_MOSI") (pinfunction "PA7/SPI1_MOSI_PA7/SPI1_MOSI") (pintype "bidirectional"))
    )
    (net (code "113") (name "unconnected-(STM1-PadPA8)") (class "Default")
      (node (ref "STM1") (pin "PA8") (pinfunction "PA8_PA8") (pintype "bidirectional"))
    )
    (net (code "114") (name "unconnected-(STM1-PadPB5)") (class "Default")
      (node (ref "STM1") (pin "PB5") (pinfunction "PB5_PB5") (pintype "bidirectional"))
    )
    (net (code "115") (name "unconnected-(STM1-PadPB6)") (class "Default")
      (node (ref "STM1") (pin "PB6") (pinfunction "PB6_PB6") (pintype "bidirectional"))
    )
    (net (code "116") (name "unconnected-(SW1-PadR)") (class "Default")
      (node (ref "SW1") (pin "R") (pinfunction "R_R") (pintype "bidirectional"))
    )
    (net (code "117") (name "unconnected-(U$1-PadPA0)") (class "Default")
      (node (ref "U$1") (pin "PA0") (pinfunction "PA0_PA0") (pintype "bidirectional"))
    )
    (net (code "118") (name "unconnected-(U$1-PadPA1)") (class "Default")
      (node (ref "U$1") (pin "PA1") (pinfunction "PA1_PA1") (pintype "bidirectional"))
    )
    (net (code "119") (name "unconnected-(U$1-PadPA2{slash}UART2_TX)") (class "Default")
      (node (ref "U$1") (pin "PA2/UART2_TX") (pinfunction "PA2/UART2_TX_PA2/UART2_TX") (pintype "bidirectional"))
    )
    (net (code "120") (name "unconnected-(U$1-PadPA3{slash}UART2_RX)") (class "Default")
      (node (ref "U$1") (pin "PA3/UART2_RX") (pinfunction "PA3/UART2_RX_PA3/UART2_RX") (pintype "bidirectional"))
    )
    (net (code "121") (name "unconnected-(U$1-PadPA4{slash}SPI1_NSS)") (class "Default")
      (node (ref "U$1") (pin "PA4/SPI1_NSS") (pinfunction "PA4/SPI1_NSS_PA4/SPI1_NSS") (pintype "bidirectional"))
    )
    (net (code "122") (name "unconnected-(U$1-PadPA6{slash}SPI1_MISO)") (class "Default")
      (node (ref "U$1") (pin "PA6/SPI1_MISO") (pinfunction "PA6/SPI1_MISO_PA6/SPI1_MISO") (pintype "bidirectional"))
    )
    (net (code "123") (name "unconnected-(U$1-PadPA7{slash}SPI1_MOSI)") (class "Default")
      (node (ref "U$1") (pin "PA7/SPI1_MOSI") (pinfunction "PA7/SPI1_MOSI_PA7/SPI1_MOSI") (pintype "bidirectional"))
    )
    (net (code "124") (name "unconnected-(U$1-PadPA8)") (class "Default")
      (node (ref "U$1") (pin "PA8") (pinfunction "PA8_PA8") (pintype "bidirectional"))
    )
    (net (code "125") (name "unconnected-(U$1-PadPB5)") (class "Default")
      (node (ref "U$1") (pin "PB5") (pinfunction "PB5_PB5") (pintype "bidirectional"))
    )
    (net (code "126") (name "unconnected-(U$1-PadPB6)") (class "Default")
      (node (ref "U$1") (pin "PB6") (pinfunction "PB6_PB6") (pintype "bidirectional"))
    )
    (net (code "127") (name "unconnected-(U$2-1PPS-PadP5)") (class "Default")
      (node (ref "U$2") (pin "P5") (pinfunction "1PPS_P5") (pintype "bidirectional"))
    )
  )
)
